# 03-FPGA_DECOUPLING.net
KiCad netlist of a schematic drawn in Altium Designer
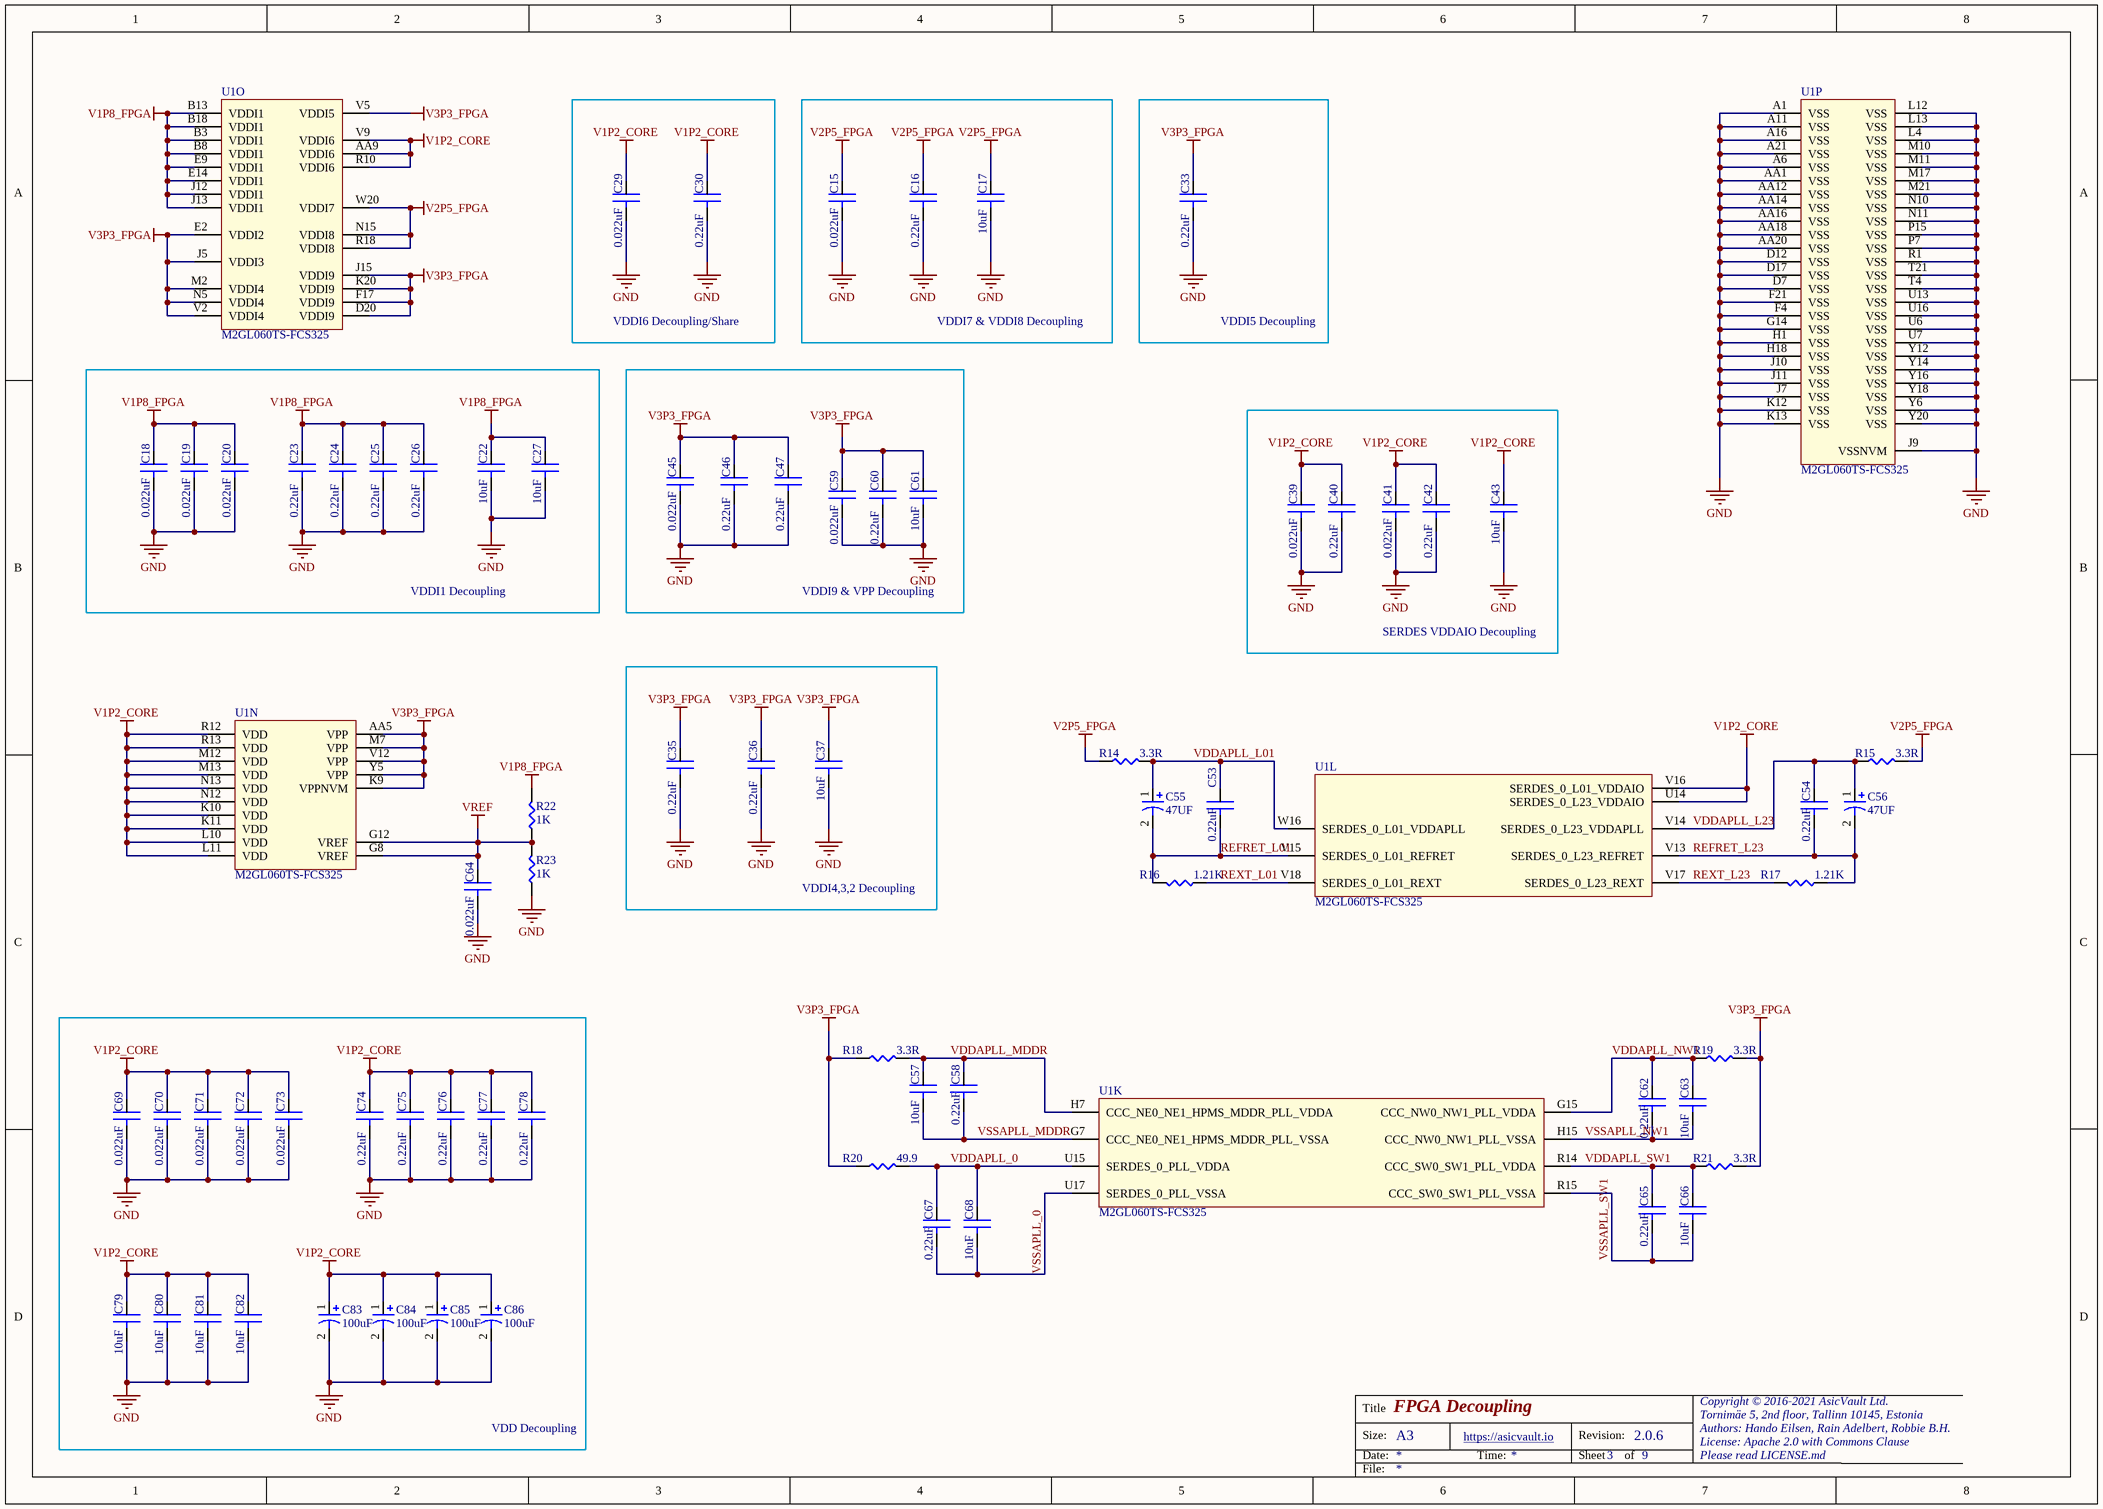
[diagram p0: 03-FPGA_DECOUPLING.SchDoc]

(export (version "E")
  (design (tool "Eeschema 10.0.6"))
  (components
    (comp (ref "C15") (value "0.022uF") (footprint "C0201") (libsource (lib "AMOLED") (part "0.022uF/0201")))
    (comp (ref "C16") (value "0.22uF") (footprint "C0201") (libsource (lib "AMOLED") (part "0.22uF/0201")))
    (comp (ref "C17") (value "10uF") (footprint "C0402") (libsource (lib "AMOLED") (part "10uF/0402")))
    (comp (ref "C18") (value "0.022uF") (footprint "C0201") (libsource (lib "AMOLED") (part "0.022uF/0201")))
    (comp (ref "C19") (value "0.022uF") (footprint "C0201") (libsource (lib "AMOLED") (part "0.022uF/0201")))
    (comp (ref "C20") (value "0.022uF") (footprint "C0201") (libsource (lib "AMOLED") (part "0.022uF/0201")))
    (comp (ref "C22") (value "10uF") (footprint "C0402") (libsource (lib "AMOLED") (part "10uF/0402")))
    (comp (ref "C23") (value "0.22uF") (footprint "C0201") (libsource (lib "AMOLED") (part "0.22uF/0201")))
    (comp (ref "C24") (value "0.22uF") (footprint "C0201") (libsource (lib "AMOLED") (part "0.22uF/0201")))
    (comp (ref "C25") (value "0.22uF") (footprint "C0201") (libsource (lib "AMOLED") (part "0.22uF/0201")))
    (comp (ref "C26") (value "0.22uF") (footprint "C0201") (libsource (lib "AMOLED") (part "0.22uF/0201")))
    (comp (ref "C27") (value "10uF") (footprint "C0402") (libsource (lib "AMOLED") (part "10uF/0402")))
    (comp (ref "C29") (value "0.022uF") (footprint "C0201") (libsource (lib "AMOLED") (part "0.022uF/0201")))
    (comp (ref "C30") (value "0.22uF") (footprint "C0201") (libsource (lib "AMOLED") (part "0.22uF/0201")))
    (comp (ref "C33") (value "0.22uF") (footprint "C0201") (libsource (lib "AMOLED") (part "0.22uF/0201")))
    (comp (ref "C35") (value "0.22uF") (footprint "C0201") (libsource (lib "AMOLED") (part "0.22uF/0201")))
    (comp (ref "C36") (value "0.22uF") (footprint "C0201") (libsource (lib "AMOLED") (part "0.22uF/0201")))
    (comp (ref "C37") (value "10uF") (footprint "C0402") (libsource (lib "AMOLED") (part "10uF/0402")))
    (comp (ref "C39") (value "0.022uF") (footprint "C0201") (libsource (lib "AMOLED") (part "0.022uF/0201")))
    (comp (ref "C40") (value "0.22uF") (footprint "C0201") (libsource (lib "AMOLED") (part "0.22uF/0201")))
    (comp (ref "C41") (value "0.022uF") (footprint "C0201") (libsource (lib "AMOLED") (part "0.022uF/0201")))
    (comp (ref "C42") (value "0.22uF") (footprint "C0201") (libsource (lib "AMOLED") (part "0.22uF/0201")))
    (comp (ref "C43") (value "10uF") (footprint "C0402") (libsource (lib "AMOLED") (part "10uF/0402")))
    (comp (ref "C45") (value "0.022uF") (footprint "C0201") (libsource (lib "AMOLED") (part "0.022uF/0201")))
    (comp (ref "C46") (value "0.22uF") (footprint "C0201") (libsource (lib "AMOLED") (part "0.22uF/0201")))
    (comp (ref "C47") (value "0.22uF") (footprint "C0201") (libsource (lib "AMOLED") (part "0.22uF/0201")))
    (comp (ref "C53") (value "0.22uF") (footprint "C0201") (libsource (lib "AMOLED") (part "0.22uF/0201")))
    (comp (ref "C54") (value "0.22uF") (footprint "C0201") (libsource (lib "AMOLED") (part "0.22uF/0201")))
    (comp (ref "C55") (value "47UF") (footprint "M0603C") (libsource (lib "AMOLED") (part "47UF/4V")))
    (comp (ref "C56") (value "47UF") (footprint "M0603C") (libsource (lib "AMOLED") (part "47UF/4V")))
    (comp (ref "C57") (value "10uF") (footprint "C0402") (libsource (lib "AMOLED") (part "10uF/0402")))
    (comp (ref "C58") (value "0.22uF") (footprint "C0201") (libsource (lib "AMOLED") (part "0.22uF/0201")))
    (comp (ref "C59") (value "0.022uF") (footprint "C0201") (libsource (lib "AMOLED") (part "0.022uF/0201")))
    (comp (ref "C60") (value "0.22uF") (footprint "C0201") (libsource (lib "AMOLED") (part "0.22uF/0201")))
    (comp (ref "C61") (value "10uF") (footprint "C0402") (libsource (lib "AMOLED") (part "10uF/0402")))
    (comp (ref "C62") (value "0.22uF") (footprint "C0201") (libsource (lib "AMOLED") (part "0.22uF/0201")))
    (comp (ref "C63") (value "10uF") (footprint "C0402") (libsource (lib "AMOLED") (part "10uF/0402")))
    (comp (ref "C64") (value "0.022uF") (footprint "C0201") (libsource (lib "AMOLED") (part "0.022uF/0201")))
    (comp (ref "C65") (value "0.22uF") (footprint "C0201") (libsource (lib "AMOLED") (part "0.22uF/0201")))
    (comp (ref "C66") (value "10uF") (footprint "C0402") (libsource (lib "AMOLED") (part "10uF/0402")))
    (comp (ref "C67") (value "0.22uF") (footprint "C0201") (libsource (lib "AMOLED") (part "0.22uF/0201")))
    (comp (ref "C68") (value "10uF") (footprint "C0402") (libsource (lib "AMOLED") (part "10uF/0402")))
    (comp (ref "C69") (value "0.022uF") (footprint "C0201") (libsource (lib "AMOLED") (part "0.022uF/0201")))
    (comp (ref "C70") (value "0.022uF") (footprint "C0201") (libsource (lib "AMOLED") (part "0.022uF/0201")))
    (comp (ref "C71") (value "0.022uF") (footprint "C0201") (libsource (lib "AMOLED") (part "0.022uF/0201")))
    (comp (ref "C72") (value "0.022uF") (footprint "C0201") (libsource (lib "AMOLED") (part "0.022uF/0201")))
    (comp (ref "C73") (value "0.022uF") (footprint "C0201") (libsource (lib "AMOLED") (part "0.022uF/0201")))
    (comp (ref "C74") (value "0.22uF") (footprint "C0201") (libsource (lib "AMOLED") (part "0.22uF/0201")))
    (comp (ref "C75") (value "0.22uF") (footprint "C0201") (libsource (lib "AMOLED") (part "0.22uF/0201")))
    (comp (ref "C76") (value "0.22uF") (footprint "C0201") (libsource (lib "AMOLED") (part "0.22uF/0201")))
    (comp (ref "C77") (value "0.22uF") (footprint "C0201") (libsource (lib "AMOLED") (part "0.22uF/0201")))
    (comp (ref "C78") (value "0.22uF") (footprint "C0201") (libsource (lib "AMOLED") (part "0.22uF/0201")))
    (comp (ref "C79") (value "10uF") (footprint "C0402") (libsource (lib "AMOLED") (part "10uF/0402")))
    (comp (ref "C80") (value "10uF") (footprint "C0402") (libsource (lib "AMOLED") (part "10uF/0402")))
    (comp (ref "C81") (value "10uF") (footprint "C0402") (libsource (lib "AMOLED") (part "10uF/0402")))
    (comp (ref "C82") (value "10uF") (footprint "C0402") (libsource (lib "AMOLED") (part "10uF/0402")))
    (comp (ref "C83") (value "100uF") (footprint "C0805T") (libsource (lib "AMOLED") (part "100uF/0805")))
    (comp (ref "C84") (value "100uF") (footprint "C0805T") (libsource (lib "AMOLED") (part "100uF/0805")))
    (comp (ref "C85") (value "100uF") (footprint "C0805T") (libsource (lib "AMOLED") (part "100uF/0805")))
    (comp (ref "C86") (value "100uF") (footprint "C0805T") (libsource (lib "AMOLED") (part "100uF/0805")))
    (comp (ref "R14")
      (value "3.3R")
      (footprint "R0201")
      (libsource (lib "Control_Board") (part "3.3R/1%/0201"))
    )
    (comp (ref "R15")
      (value "3.3R")
      (footprint "R0201")
      (libsource (lib "Control_Board") (part "3.3R/1%/0201"))
    )
    (comp (ref "R16")
      (value "1.21K")
      (footprint "R0201")
      (libsource (lib "Control_Board") (part "1.21K/1%/0201"))
    )
    (comp (ref "R17")
      (value "1.21K")
      (footprint "R0201")
      (libsource (lib "Control_Board") (part "1.21K/1%/0201"))
    )
    (comp (ref "R18")
      (value "3.3R")
      (footprint "R0201")
      (libsource (lib "Control_Board") (part "3.3R/1%/0201"))
    )
    (comp (ref "R19")
      (value "3.3R")
      (footprint "R0201")
      (libsource (lib "Control_Board") (part "3.3R/1%/0201"))
    )
    (comp (ref "R20")
      (value "49.9")
      (footprint "R0201")
      (libsource (lib "Control_Board") (part "49.9/1%/0201"))
    )
    (comp (ref "R21")
      (value "3.3R")
      (footprint "R0201")
      (libsource (lib "Control_Board") (part "3.3R/1%/0201"))
    )
    (comp (ref "R22") (value "1K") (footprint "R0201") (libsource (lib "Control_Board") (part "1K/1%/0201")))
    (comp (ref "R23") (value "1K") (footprint "R0201") (libsource (lib "Control_Board") (part "1K/1%/0201")))
    (comp (ref "U1")
      (value "M2GL060TS-FCS325")
      (footprint "FCS325-OPT1")
      (libsource (lib "Board3") (part "M2GL060TS-FCS325"))
    )
  )
  (nets
    (net (code "1") (name "/REFRET_L01") (class "Default")
      (node (ref "C53") (pin "2") (pinfunction "2_2") (pintype "passive"))
      (node (ref "C55") (pin "2") (pinfunction "2_2") (pintype "passive"))
      (node (ref "R16") (pin "2") (pinfunction "2_2") (pintype "passive"))
      (node (ref "U1") (pin "V15") (pinfunction "SERDES_0_L01_REFRET_V15") (pintype "passive"))
    )
    (net (code "2") (name "/REFRET_L23") (class "Default")
      (node (ref "C54") (pin "2") (pinfunction "2_2") (pintype "passive"))
      (node (ref "C56") (pin "2") (pinfunction "2_2") (pintype "passive"))
      (node (ref "R17") (pin "1") (pinfunction "1_1") (pintype "passive"))
      (node (ref "U1") (pin "V13") (pinfunction "SERDES_0_L23_REFRET_V13") (pintype "passive"))
    )
    (net (code "3") (name "/REXT_L01") (class "Default")
      (node (ref "R16") (pin "1") (pinfunction "1_1") (pintype "passive"))
      (node (ref "U1") (pin "V18") (pinfunction "SERDES_0_L01_REXT_V18") (pintype "passive"))
    )
    (net (code "4") (name "/REXT_L23") (class "Default")
      (node (ref "R17") (pin "2") (pinfunction "2_2") (pintype "passive"))
      (node (ref "U1") (pin "V17") (pinfunction "SERDES_0_L23_REXT_V17") (pintype "passive"))
    )
    (net (code "5") (name "/VDDAPLL_0") (class "Default")
      (node (ref "C67") (pin "1") (pinfunction "1_1") (pintype "passive"))
      (node (ref "C68") (pin "1") (pinfunction "1_1") (pintype "passive"))
      (node (ref "R20") (pin "2") (pinfunction "2_2") (pintype "passive"))
      (node (ref "U1") (pin "U15") (pinfunction "SERDES_0_PLL_VDDA_U15") (pintype "power_in"))
    )
    (net (code "6") (name "/VDDAPLL_L01") (class "Default")
      (node (ref "C53") (pin "1") (pinfunction "1_1") (pintype "passive"))
      (node (ref "C55") (pin "1") (pinfunction "1_1") (pintype "passive"))
      (node (ref "R14") (pin "2") (pinfunction "2_2") (pintype "passive"))
      (node (ref "U1") (pin "W16") (pinfunction "SERDES_0_L01_VDDAPLL_W16") (pintype "power_in"))
    )
    (net (code "7") (name "/VDDAPLL_L23") (class "Default")
      (node (ref "C54") (pin "1") (pinfunction "1_1") (pintype "passive"))
      (node (ref "C56") (pin "1") (pinfunction "1_1") (pintype "passive"))
      (node (ref "R15") (pin "1") (pinfunction "1_1") (pintype "passive"))
      (node (ref "U1") (pin "V14") (pinfunction "SERDES_0_L23_VDDAPLL_V14") (pintype "power_in"))
    )
    (net (code "8") (name "/VDDAPLL_MDDR") (class "Default")
      (node (ref "C57") (pin "1") (pinfunction "1_1") (pintype "passive"))
      (node (ref "C58") (pin "1") (pinfunction "1_1") (pintype "passive"))
      (node (ref "R18") (pin "2") (pinfunction "2_2") (pintype "passive"))
      (node (ref "U1") (pin "H7") (pinfunction "CCC_NE0_NE1_HPMS_MDDR_PLL_VDDA_H7") (pintype "power_in"))
    )
    (net (code "9") (name "/VDDAPLL_NW1") (class "Default")
      (node (ref "C62") (pin "1") (pinfunction "1_1") (pintype "passive"))
      (node (ref "C63") (pin "1") (pinfunction "1_1") (pintype "passive"))
      (node (ref "R19") (pin "1") (pinfunction "1_1") (pintype "passive"))
      (node (ref "U1") (pin "G15") (pinfunction "CCC_NW0_NW1_PLL_VDDA_G15") (pintype "power_in"))
    )
    (net (code "10") (name "/VDDAPLL_SW1") (class "Default")
      (node (ref "C65") (pin "1") (pinfunction "1_1") (pintype "passive"))
      (node (ref "C66") (pin "1") (pinfunction "1_1") (pintype "passive"))
      (node (ref "R21") (pin "1") (pinfunction "1_1") (pintype "passive"))
      (node (ref "U1") (pin "R14") (pinfunction "CCC_SW0_SW1_PLL_VDDA_R14") (pintype "power_in"))
    )
    (net (code "11") (name "/VSSAPLL_0") (class "Default")
      (node (ref "C67") (pin "2") (pinfunction "2_2") (pintype "passive"))
      (node (ref "C68") (pin "2") (pinfunction "2_2") (pintype "passive"))
      (node (ref "U1") (pin "U17") (pinfunction "SERDES_0_PLL_VSSA_U17") (pintype "power_in"))
    )
    (net (code "12") (name "/VSSAPLL_MDDR") (class "Default")
      (node (ref "C57") (pin "2") (pinfunction "2_2") (pintype "passive"))
      (node (ref "C58") (pin "2") (pinfunction "2_2") (pintype "passive"))
      (node (ref "U1") (pin "G7") (pinfunction "CCC_NE0_NE1_HPMS_MDDR_PLL_VSSA_G7") (pintype "power_in"))
    )
    (net (code "13") (name "/VSSAPLL_NW1") (class "Default")
      (node (ref "C62") (pin "2") (pinfunction "2_2") (pintype "passive"))
      (node (ref "C63") (pin "2") (pinfunction "2_2") (pintype "passive"))
      (node (ref "U1") (pin "H15") (pinfunction "CCC_NW0_NW1_PLL_VSSA_H15") (pintype "power_in"))
    )
    (net (code "14") (name "/VSSAPLL_SW1") (class "Default")
      (node (ref "C65") (pin "2") (pinfunction "2_2") (pintype "passive"))
      (node (ref "C66") (pin "2") (pinfunction "2_2") (pintype "passive"))
      (node (ref "U1") (pin "R15") (pinfunction "CCC_SW0_SW1_PLL_VSSA_R15") (pintype "power_in"))
    )
    (net (code "15") (name "GND") (class "Default")
      (node (ref "C15") (pin "2") (pinfunction "2_2") (pintype "passive"))
      (node (ref "C16") (pin "2") (pinfunction "2_2") (pintype "passive"))
      (node (ref "C17") (pin "2") (pinfunction "2_2") (pintype "passive"))
      (node (ref "C18") (pin "2") (pinfunction "2_2") (pintype "passive"))
      (node (ref "C19") (pin "2") (pinfunction "2_2") (pintype "passive"))
      (node (ref "C20") (pin "2") (pinfunction "2_2") (pintype "passive"))
      (node (ref "C22") (pin "2") (pinfunction "2_2") (pintype "passive"))
      (node (ref "C23") (pin "2") (pinfunction "2_2") (pintype "passive"))
      (node (ref "C24") (pin "2") (pinfunction "2_2") (pintype "passive"))
      (node (ref "C25") (pin "2") (pinfunction "2_2") (pintype "passive"))
      (node (ref "C26") (pin "2") (pinfunction "2_2") (pintype "passive"))
      (node (ref "C27") (pin "2") (pinfunction "2_2") (pintype "passive"))
      (node (ref "C29") (pin "2") (pinfunction "2_2") (pintype "passive"))
      (node (ref "C30") (pin "2") (pinfunction "2_2") (pintype "passive"))
      (node (ref "C33") (pin "2") (pinfunction "2_2") (pintype "passive"))
      (node (ref "C35") (pin "2") (pinfunction "2_2") (pintype "passive"))
      (node (ref "C36") (pin "2") (pinfunction "2_2") (pintype "passive"))
      (node (ref "C37") (pin "2") (pinfunction "2_2") (pintype "passive"))
      (node (ref "C39") (pin "2") (pinfunction "2_2") (pintype "passive"))
      (node (ref "C40") (pin "2") (pinfunction "2_2") (pintype "passive"))
      (node (ref "C41") (pin "2") (pinfunction "2_2") (pintype "passive"))
      (node (ref "C42") (pin "2") (pinfunction "2_2") (pintype "passive"))
      (node (ref "C43") (pin "2") (pinfunction "2_2") (pintype "passive"))
      (node (ref "C45") (pin "2") (pinfunction "2_2") (pintype "passive"))
      (node (ref "C46") (pin "2") (pinfunction "2_2") (pintype "passive"))
      (node (ref "C47") (pin "2") (pinfunction "2_2") (pintype "passive"))
      (node (ref "C59") (pin "2") (pinfunction "2_2") (pintype "passive"))
      (node (ref "C60") (pin "2") (pinfunction "2_2") (pintype "passive"))
      (node (ref "C61") (pin "2") (pinfunction "2_2") (pintype "passive"))
      (node (ref "C64") (pin "2") (pinfunction "2_2") (pintype "passive"))
      (node (ref "C69") (pin "2") (pinfunction "2_2") (pintype "passive"))
      (node (ref "C70") (pin "2") (pinfunction "2_2") (pintype "passive"))
      (node (ref "C71") (pin "2") (pinfunction "2_2") (pintype "passive"))
      (node (ref "C72") (pin "2") (pinfunction "2_2") (pintype "passive"))
      (node (ref "C73") (pin "2") (pinfunction "2_2") (pintype "passive"))
      (node (ref "C74") (pin "2") (pinfunction "2_2") (pintype "passive"))
      (node (ref "C75") (pin "2") (pinfunction "2_2") (pintype "passive"))
      (node (ref "C76") (pin "2") (pinfunction "2_2") (pintype "passive"))
      (node (ref "C77") (pin "2") (pinfunction "2_2") (pintype "passive"))
      (node (ref "C78") (pin "2") (pinfunction "2_2") (pintype "passive"))
      (node (ref "C79") (pin "2") (pinfunction "2_2") (pintype "passive"))
      (node (ref "C80") (pin "2") (pinfunction "2_2") (pintype "passive"))
      (node (ref "C81") (pin "2") (pinfunction "2_2") (pintype "passive"))
      (node (ref "C82") (pin "2") (pinfunction "2_2") (pintype "passive"))
      (node (ref "C83") (pin "2") (pinfunction "2_2") (pintype "passive"))
      (node (ref "C84") (pin "2") (pinfunction "2_2") (pintype "passive"))
      (node (ref "C85") (pin "2") (pinfunction "2_2") (pintype "passive"))
      (node (ref "C86") (pin "2") (pinfunction "2_2") (pintype "passive"))
      (node (ref "R23") (pin "1") (pinfunction "1_1") (pintype "passive"))
      (node (ref "U1") (pin "A1") (pinfunction "VSS_A1") (pintype "passive"))
      (node (ref "U1") (pin "A11") (pinfunction "VSS_A11") (pintype "passive"))
      (node (ref "U1") (pin "A16") (pinfunction "VSS_A16") (pintype "passive"))
      (node (ref "U1") (pin "A21") (pinfunction "VSS_A21") (pintype "passive"))
      (node (ref "U1") (pin "A6") (pinfunction "VSS_A6") (pintype "passive"))
      (node (ref "U1") (pin "AA1") (pinfunction "VSS_AA1") (pintype "passive"))
      (node (ref "U1") (pin "AA12") (pinfunction "VSS_AA12") (pintype "passive"))
      (node (ref "U1") (pin "AA14") (pinfunction "VSS_AA14") (pintype "passive"))
      (node (ref "U1") (pin "AA16") (pinfunction "VSS_AA16") (pintype "passive"))
      (node (ref "U1") (pin "AA18") (pinfunction "VSS_AA18") (pintype "passive"))
      (node (ref "U1") (pin "AA20") (pinfunction "VSS_AA20") (pintype "passive"))
      (node (ref "U1") (pin "D12") (pinfunction "VSS_D12") (pintype "passive"))
      (node (ref "U1") (pin "D17") (pinfunction "VSS_D17") (pintype "passive"))
      (node (ref "U1") (pin "D7") (pinfunction "VSS_D7") (pintype "passive"))
      (node (ref "U1") (pin "F21") (pinfunction "VSS_F21") (pintype "passive"))
      (node (ref "U1") (pin "F4") (pinfunction "VSS_F4") (pintype "passive"))
      (node (ref "U1") (pin "G14") (pinfunction "VSS_G14") (pintype "passive"))
      (node (ref "U1") (pin "H1") (pinfunction "VSS_H1") (pintype "passive"))
      (node (ref "U1") (pin "H18") (pinfunction "VSS_H18") (pintype "passive"))
      (node (ref "U1") (pin "J10") (pinfunction "VSS_J10") (pintype "passive"))
      (node (ref "U1") (pin "J11") (pinfunction "VSS_J11") (pintype "passive"))
      (node (ref "U1") (pin "J7") (pinfunction "VSS_J7") (pintype "passive"))
      (node (ref "U1") (pin "J9") (pinfunction "VSSNVM_J9") (pintype "passive"))
      (node (ref "U1") (pin "K12") (pinfunction "VSS_K12") (pintype "passive"))
      (node (ref "U1") (pin "K13") (pinfunction "VSS_K13") (pintype "passive"))
      (node (ref "U1") (pin "L12") (pinfunction "VSS_L12") (pintype "passive"))
      (node (ref "U1") (pin "L13") (pinfunction "VSS_L13") (pintype "passive"))
      (node (ref "U1") (pin "L4") (pinfunction "VSS_L4") (pintype "passive"))
      (node (ref "U1") (pin "M10") (pinfunction "VSS_M10") (pintype "passive"))
      (node (ref "U1") (pin "M11") (pinfunction "VSS_M11") (pintype "passive"))
      (node (ref "U1") (pin "M17") (pinfunction "VSS_M17") (pintype "passive"))
      (node (ref "U1") (pin "M21") (pinfunction "VSS_M21") (pintype "passive"))
      (node (ref "U1") (pin "N10") (pinfunction "VSS_N10") (pintype "passive"))
      (node (ref "U1") (pin "N11") (pinfunction "VSS_N11") (pintype "passive"))
      (node (ref "U1") (pin "P15") (pinfunction "VSS_P15") (pintype "passive"))
      (node (ref "U1") (pin "P7") (pinfunction "VSS_P7") (pintype "passive"))
      (node (ref "U1") (pin "R1") (pinfunction "VSS_R1") (pintype "passive"))
      (node (ref "U1") (pin "T21") (pinfunction "VSS_T21") (pintype "passive"))
      (node (ref "U1") (pin "T4") (pinfunction "VSS_T4") (pintype "passive"))
      (node (ref "U1") (pin "U13") (pinfunction "VSS_U13") (pintype "passive"))
      (node (ref "U1") (pin "U16") (pinfunction "VSS_U16") (pintype "passive"))
      (node (ref "U1") (pin "U6") (pinfunction "VSS_U6") (pintype "passive"))
      (node (ref "U1") (pin "U7") (pinfunction "VSS_U7") (pintype "passive"))
      (node (ref "U1") (pin "Y12") (pinfunction "VSS_Y12") (pintype "passive"))
      (node (ref "U1") (pin "Y14") (pinfunction "VSS_Y14") (pintype "passive"))
      (node (ref "U1") (pin "Y16") (pinfunction "VSS_Y16") (pintype "passive"))
      (node (ref "U1") (pin "Y18") (pinfunction "VSS_Y18") (pintype "passive"))
      (node (ref "U1") (pin "Y20") (pinfunction "VSS_Y20") (pintype "passive"))
      (node (ref "U1") (pin "Y6") (pinfunction "VSS_Y6") (pintype "passive"))
    )
    (net (code "16") (name "V1P2_CORE") (class "Default")
      (node (ref "C29") (pin "1") (pinfunction "1_1") (pintype "passive"))
      (node (ref "C30") (pin "1") (pinfunction "1_1") (pintype "passive"))
      (node (ref "C39") (pin "1") (pinfunction "1_1") (pintype "passive"))
      (node (ref "C40") (pin "1") (pinfunction "1_1") (pintype "passive"))
      (node (ref "C41") (pin "1") (pinfunction "1_1") (pintype "passive"))
      (node (ref "C42") (pin "1") (pinfunction "1_1") (pintype "passive"))
      (node (ref "C43") (pin "1") (pinfunction "1_1") (pintype "passive"))
      (node (ref "C69") (pin "1") (pinfunction "1_1") (pintype "passive"))
      (node (ref "C70") (pin "1") (pinfunction "1_1") (pintype "passive"))
      (node (ref "C71") (pin "1") (pinfunction "1_1") (pintype "passive"))
      (node (ref "C72") (pin "1") (pinfunction "1_1") (pintype "passive"))
      (node (ref "C73") (pin "1") (pinfunction "1_1") (pintype "passive"))
      (node (ref "C74") (pin "1") (pinfunction "1_1") (pintype "passive"))
      (node (ref "C75") (pin "1") (pinfunction "1_1") (pintype "passive"))
      (node (ref "C76") (pin "1") (pinfunction "1_1") (pintype "passive"))
      (node (ref "C77") (pin "1") (pinfunction "1_1") (pintype "passive"))
      (node (ref "C78") (pin "1") (pinfunction "1_1") (pintype "passive"))
      (node (ref "C79") (pin "1") (pinfunction "1_1") (pintype "passive"))
      (node (ref "C80") (pin "1") (pinfunction "1_1") (pintype "passive"))
      (node (ref "C81") (pin "1") (pinfunction "1_1") (pintype "passive"))
      (node (ref "C82") (pin "1") (pinfunction "1_1") (pintype "passive"))
      (node (ref "C83") (pin "1") (pinfunction "1_1") (pintype "passive"))
      (node (ref "C84") (pin "1") (pinfunction "1_1") (pintype "passive"))
      (node (ref "C85") (pin "1") (pinfunction "1_1") (pintype "passive"))
      (node (ref "C86") (pin "1") (pinfunction "1_1") (pintype "passive"))
      (node (ref "U1") (pin "AA9") (pinfunction "VDDI6_AA9") (pintype "power_in"))
      (node (ref "U1") (pin "K10") (pinfunction "VDD_K10") (pintype "power_in"))
      (node (ref "U1") (pin "K11") (pinfunction "VDD_K11") (pintype "power_in"))
      (node (ref "U1") (pin "L10") (pinfunction "VDD_L10") (pintype "power_in"))
      (node (ref "U1") (pin "L11") (pinfunction "VDD_L11") (pintype "power_in"))
      (node (ref "U1") (pin "M12") (pinfunction "VDD_M12") (pintype "power_in"))
      (node (ref "U1") (pin "M13") (pinfunction "VDD_M13") (pintype "power_in"))
      (node (ref "U1") (pin "N12") (pinfunction "VDD_N12") (pintype "power_in"))
      (node (ref "U1") (pin "N13") (pinfunction "VDD_N13") (pintype "power_in"))
      (node (ref "U1") (pin "R10") (pinfunction "VDDI6_R10") (pintype "power_in"))
      (node (ref "U1") (pin "R12") (pinfunction "VDD_R12") (pintype "power_in"))
      (node (ref "U1") (pin "R13") (pinfunction "VDD_R13") (pintype "power_in"))
      (node (ref "U1") (pin "U14") (pinfunction "SERDES_0_L23_VDDAIO_U14") (pintype "power_in"))
      (node (ref "U1") (pin "V16") (pinfunction "SERDES_0_L01_VDDAIO_V16") (pintype "power_in"))
      (node (ref "U1") (pin "V9") (pinfunction "VDDI6_V9") (pintype "power_in"))
    )
    (net (code "17") (name "V1P8_FPGA") (class "Default")
      (node (ref "C18") (pin "1") (pinfunction "1_1") (pintype "passive"))
      (node (ref "C19") (pin "1") (pinfunction "1_1") (pintype "passive"))
      (node (ref "C20") (pin "1") (pinfunction "1_1") (pintype "passive"))
      (node (ref "C22") (pin "1") (pinfunction "1_1") (pintype "passive"))
      (node (ref "C23") (pin "1") (pinfunction "1_1") (pintype "passive"))
      (node (ref "C24") (pin "1") (pinfunction "1_1") (pintype "passive"))
      (node (ref "C25") (pin "1") (pinfunction "1_1") (pintype "passive"))
      (node (ref "C26") (pin "1") (pinfunction "1_1") (pintype "passive"))
      (node (ref "C27") (pin "1") (pinfunction "1_1") (pintype "passive"))
      (node (ref "R22") (pin "2") (pinfunction "2_2") (pintype "passive"))
      (node (ref "U1") (pin "B13") (pinfunction "VDDI1_B13") (pintype "power_in"))
      (node (ref "U1") (pin "B18") (pinfunction "VDDI1_B18") (pintype "power_in"))
      (node (ref "U1") (pin "B3") (pinfunction "VDDI1_B3") (pintype "power_in"))
      (node (ref "U1") (pin "B8") (pinfunction "VDDI1_B8") (pintype "power_in"))
      (node (ref "U1") (pin "E14") (pinfunction "VDDI1_E14") (pintype "power_in"))
      (node (ref "U1") (pin "E9") (pinfunction "VDDI1_E9") (pintype "power_in"))
      (node (ref "U1") (pin "J12") (pinfunction "VDDI1_J12") (pintype "power_in"))
      (node (ref "U1") (pin "J13") (pinfunction "VDDI1_J13") (pintype "power_in"))
    )
    (net (code "18") (name "V2P5_FPGA") (class "Default")
      (node (ref "C15") (pin "1") (pinfunction "1_1") (pintype "passive"))
      (node (ref "C16") (pin "1") (pinfunction "1_1") (pintype "passive"))
      (node (ref "C17") (pin "1") (pinfunction "1_1") (pintype "passive"))
      (node (ref "R14") (pin "1") (pinfunction "1_1") (pintype "passive"))
      (node (ref "R15") (pin "2") (pinfunction "2_2") (pintype "passive"))
      (node (ref "U1") (pin "N15") (pinfunction "VDDI8_N15") (pintype "power_in"))
      (node (ref "U1") (pin "R18") (pinfunction "VDDI8_R18") (pintype "power_in"))
      (node (ref "U1") (pin "W20") (pinfunction "VDDI7_W20") (pintype "power_in"))
    )
    (net (code "19") (name "V3P3_FPGA") (class "Default")
      (node (ref "C33") (pin "1") (pinfunction "1_1") (pintype "passive"))
      (node (ref "C35") (pin "1") (pinfunction "1_1") (pintype "passive"))
      (node (ref "C36") (pin "1") (pinfunction "1_1") (pintype "passive"))
      (node (ref "C37") (pin "1") (pinfunction "1_1") (pintype "passive"))
      (node (ref "C45") (pin "1") (pinfunction "1_1") (pintype "passive"))
      (node (ref "C46") (pin "1") (pinfunction "1_1") (pintype "passive"))
      (node (ref "C47") (pin "1") (pinfunction "1_1") (pintype "passive"))
      (node (ref "C59") (pin "1") (pinfunction "1_1") (pintype "passive"))
      (node (ref "C60") (pin "1") (pinfunction "1_1") (pintype "passive"))
      (node (ref "C61") (pin "1") (pinfunction "1_1") (pintype "passive"))
      (node (ref "R18") (pin "1") (pinfunction "1_1") (pintype "passive"))
      (node (ref "R19") (pin "2") (pinfunction "2_2") (pintype "passive"))
      (node (ref "R20") (pin "1") (pinfunction "1_1") (pintype "passive"))
      (node (ref "R21") (pin "2") (pinfunction "2_2") (pintype "passive"))
      (node (ref "U1") (pin "AA5") (pinfunction "VPP_AA5") (pintype "power_in"))
      (node (ref "U1") (pin "D20") (pinfunction "VDDI9_D20") (pintype "power_in"))
      (node (ref "U1") (pin "E2") (pinfunction "VDDI2_E2") (pintype "power_in"))
      (node (ref "U1") (pin "F17") (pinfunction "VDDI9_F17") (pintype "power_in"))
      (node (ref "U1") (pin "J15") (pinfunction "VDDI9_J15") (pintype "power_in"))
      (node (ref "U1") (pin "J5") (pinfunction "VDDI3_J5") (pintype "power_in"))
      (node (ref "U1") (pin "K20") (pinfunction "VDDI9_K20") (pintype "power_in"))
      (node (ref "U1") (pin "K9") (pinfunction "VPPNVM_K9") (pintype "power_in"))
      (node (ref "U1") (pin "M2") (pinfunction "VDDI4_M2") (pintype "power_in"))
      (node (ref "U1") (pin "M7") (pinfunction "VPP_M7") (pintype "power_in"))
      (node (ref "U1") (pin "N5") (pinfunction "VDDI4_N5") (pintype "power_in"))
      (node (ref "U1") (pin "V12") (pinfunction "VPP_V12") (pintype "power_in"))
      (node (ref "U1") (pin "V2") (pinfunction "VDDI4_V2") (pintype "power_in"))
      (node (ref "U1") (pin "V5") (pinfunction "VDDI5_V5") (pintype "power_in"))
      (node (ref "U1") (pin "Y5") (pinfunction "VPP_Y5") (pintype "power_in"))
    )
    (net (code "20") (name "VREF") (class "Default")
      (node (ref "C64") (pin "1") (pinfunction "1_1") (pintype "passive"))
      (node (ref "R22") (pin "1") (pinfunction "1_1") (pintype "passive"))
      (node (ref "R23") (pin "2") (pinfunction "2_2") (pintype "passive"))
      (node (ref "U1") (pin "G12") (pinfunction "VREF_G12") (pintype "passive"))
      (node (ref "U1") (pin "G8") (pinfunction "VREF_G8") (pintype "passive"))
    )
  )
)
